# projeto_2.net
KiCad netlist of a schematic drawn in EAGLE
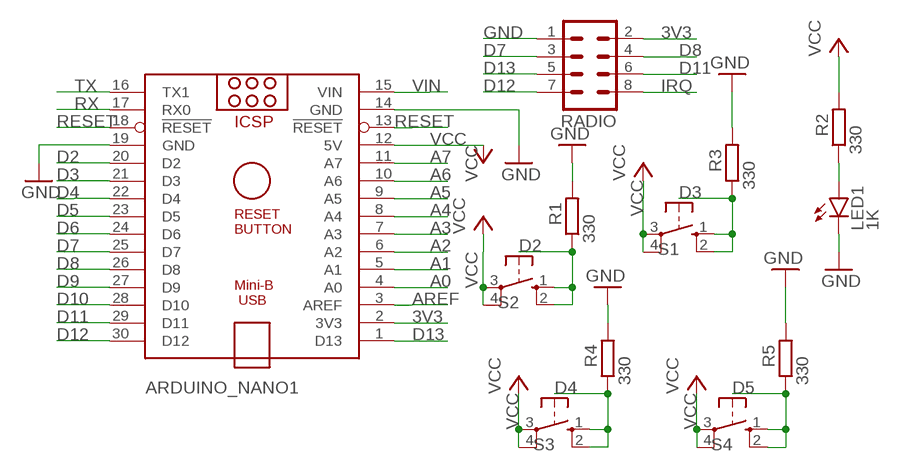
[diagram p0: schematic, sheet 1]

(export (version "E")
  (design (tool "Eeschema 10.0.6"))
  (components
    (comp (ref "ARDUINO_NANO1")
      (value "ARDUINO_NANO")
      (footprint "eagle-import:ARDUINO_NANO")
      (libsource (lib "eagle-import") (part "ARDUINO_NANO"))
    )
    (comp (ref "LED1")
      (value "1K")
      (footprint "eagle-import:LED5MM")
      (libsource (lib "eagle-import") (part "LED5MM"))
    )
    (comp (ref "R1")
      (value "330")
      (footprint "eagle-import:0204_7")
      (libsource (lib "eagle-import") (part "R-EU_0204/7"))
    )
    (comp (ref "R2")
      (value "330")
      (footprint "eagle-import:0204_7")
      (libsource (lib "eagle-import") (part "R-EU_0204/7"))
    )
    (comp (ref "R3")
      (value "330")
      (footprint "eagle-import:0204_7")
      (libsource (lib "eagle-import") (part "R-EU_0204/7"))
    )
    (comp (ref "R4")
      (value "330")
      (footprint "eagle-import:0204_7")
      (libsource (lib "eagle-import") (part "R-EU_0204/7"))
    )
    (comp (ref "R5")
      (value "330")
      (footprint "eagle-import:0204_7")
      (libsource (lib "eagle-import") (part "R-EU_0204/7"))
    )
    (comp (ref "RADIO")
      (value "MA04-2")
      (footprint "eagle-import:MA04-2")
      (libsource (lib "eagle-import") (part "MA04-2"))
    )
    (comp (ref "S1")
      (value "CHAVE 1")
      (footprint "eagle-import:B3F-10XX")
      (fields (field (name "MPN") "B3F-1000"))
      (libsource (lib "eagle-import") (part "10-XX"))
    )
    (comp (ref "S2")
      (value "CHAVE 1")
      (footprint "eagle-import:B3F-10XX")
      (fields (field (name "MPN") "B3F-1000"))
      (libsource (lib "eagle-import") (part "10-XX"))
    )
    (comp (ref "S3")
      (value "CHAVE 1")
      (footprint "eagle-import:B3F-10XX")
      (fields (field (name "MPN") "B3F-1000"))
      (libsource (lib "eagle-import") (part "10-XX"))
    )
    (comp (ref "S4")
      (value "CHAVE 1")
      (footprint "eagle-import:B3F-10XX")
      (fields (field (name "MPN") "B3F-1000"))
      (libsource (lib "eagle-import") (part "10-XX"))
    )
  )
  (nets
    (net (code "1") (name "/3V3") (class "Default")
      (node (ref "ARDUINO_NANO1") (pin "2") (pinfunction "3V3_2") (pintype "output"))
      (node (ref "RADIO") (pin "2") (pinfunction "2_2") (pintype "passive"))
    )
    (net (code "2") (name "/A0") (class "Default")
      (node (ref "ARDUINO_NANO1") (pin "4") (pinfunction "A0_4") (pintype "bidirectional"))
    )
    (net (code "3") (name "/A1") (class "Default")
      (node (ref "ARDUINO_NANO1") (pin "5") (pinfunction "A1_5") (pintype "bidirectional"))
    )
    (net (code "4") (name "/A2") (class "Default")
      (node (ref "ARDUINO_NANO1") (pin "6") (pinfunction "A2_6") (pintype "bidirectional"))
    )
    (net (code "5") (name "/A3") (class "Default")
      (node (ref "ARDUINO_NANO1") (pin "7") (pinfunction "A3_7") (pintype "bidirectional"))
    )
    (net (code "6") (name "/A4") (class "Default")
      (node (ref "ARDUINO_NANO1") (pin "8") (pinfunction "A4_8") (pintype "bidirectional"))
    )
    (net (code "7") (name "/A5") (class "Default")
      (node (ref "ARDUINO_NANO1") (pin "9") (pinfunction "A5_9") (pintype "bidirectional"))
    )
    (net (code "8") (name "/A6") (class "Default")
      (node (ref "ARDUINO_NANO1") (pin "10") (pinfunction "A6_10") (pintype "bidirectional"))
    )
    (net (code "9") (name "/A7") (class "Default")
      (node (ref "ARDUINO_NANO1") (pin "11") (pinfunction "A7_11") (pintype "bidirectional"))
    )
    (net (code "10") (name "/AREF") (class "Default")
      (node (ref "ARDUINO_NANO1") (pin "3") (pinfunction "AREF_3") (pintype "input"))
    )
    (net (code "11") (name "/D2") (class "Default")
      (node (ref "ARDUINO_NANO1") (pin "20") (pinfunction "D2_20") (pintype "bidirectional"))
      (node (ref "R1") (pin "1") (pinfunction "1_1") (pintype "passive"))
      (node (ref "S2") (pin "1") (pinfunction "S_1") (pintype "passive"))
      (node (ref "S2") (pin "2") (pinfunction "S1_2") (pintype "passive"))
    )
    (net (code "12") (name "/D3") (class "Default")
      (node (ref "ARDUINO_NANO1") (pin "21") (pinfunction "D3_21") (pintype "bidirectional"))
      (node (ref "R3") (pin "1") (pinfunction "1_1") (pintype "passive"))
      (node (ref "S1") (pin "1") (pinfunction "S_1") (pintype "passive"))
      (node (ref "S1") (pin "2") (pinfunction "S1_2") (pintype "passive"))
    )
    (net (code "13") (name "/D4") (class "Default")
      (node (ref "ARDUINO_NANO1") (pin "22") (pinfunction "D4_22") (pintype "bidirectional"))
      (node (ref "R4") (pin "1") (pinfunction "1_1") (pintype "passive"))
      (node (ref "S3") (pin "1") (pinfunction "S_1") (pintype "passive"))
      (node (ref "S3") (pin "2") (pinfunction "S1_2") (pintype "passive"))
    )
    (net (code "14") (name "/D5") (class "Default")
      (node (ref "ARDUINO_NANO1") (pin "23") (pinfunction "D5_23") (pintype "bidirectional"))
      (node (ref "R5") (pin "1") (pinfunction "1_1") (pintype "passive"))
      (node (ref "S4") (pin "1") (pinfunction "S_1") (pintype "passive"))
      (node (ref "S4") (pin "2") (pinfunction "S1_2") (pintype "passive"))
    )
    (net (code "15") (name "/D6") (class "Default")
      (node (ref "ARDUINO_NANO1") (pin "24") (pinfunction "D6_24") (pintype "bidirectional"))
    )
    (net (code "16") (name "/D7") (class "Default")
      (node (ref "ARDUINO_NANO1") (pin "25") (pinfunction "D7_25") (pintype "bidirectional"))
      (node (ref "RADIO") (pin "3") (pinfunction "3_3") (pintype "passive"))
    )
    (net (code "17") (name "/D8") (class "Default")
      (node (ref "ARDUINO_NANO1") (pin "26") (pinfunction "D8_26") (pintype "bidirectional"))
      (node (ref "RADIO") (pin "4") (pinfunction "4_4") (pintype "passive"))
    )
    (net (code "18") (name "/D9") (class "Default")
      (node (ref "ARDUINO_NANO1") (pin "27") (pinfunction "D9_27") (pintype "bidirectional"))
    )
    (net (code "19") (name "/D10") (class "Default")
      (node (ref "ARDUINO_NANO1") (pin "28") (pinfunction "D10_28") (pintype "bidirectional"))
    )
    (net (code "20") (name "/D11") (class "Default")
      (node (ref "ARDUINO_NANO1") (pin "29") (pinfunction "D11_29") (pintype "bidirectional"))
      (node (ref "RADIO") (pin "6") (pinfunction "6_6") (pintype "passive"))
    )
    (net (code "21") (name "/D12") (class "Default")
      (node (ref "ARDUINO_NANO1") (pin "30") (pinfunction "D12_30") (pintype "bidirectional"))
      (node (ref "RADIO") (pin "7") (pinfunction "7_7") (pintype "passive"))
    )
    (net (code "22") (name "/D13") (class "Default")
      (node (ref "ARDUINO_NANO1") (pin "1") (pinfunction "D13_1") (pintype "bidirectional"))
      (node (ref "RADIO") (pin "5") (pinfunction "5_5") (pintype "passive"))
    )
    (net (code "23") (name "/IRQ") (class "Default")
      (node (ref "RADIO") (pin "8") (pinfunction "8_8") (pintype "passive"))
    )
    (net (code "24") (name "/RESET") (class "Default")
      (node (ref "ARDUINO_NANO1") (pin "13") (pinfunction "~{RESET}_13") (pintype "input"))
      (node (ref "ARDUINO_NANO1") (pin "18") (pinfunction "~{RESET}_18") (pintype "input"))
    )
    (net (code "25") (name "/RX") (class "Default")
      (node (ref "ARDUINO_NANO1") (pin "17") (pinfunction "RX0_17") (pintype "bidirectional"))
    )
    (net (code "26") (name "/TX") (class "Default")
      (node (ref "ARDUINO_NANO1") (pin "16") (pinfunction "TX1_16") (pintype "bidirectional"))
    )
    (net (code "27") (name "/VIN") (class "Default")
      (node (ref "ARDUINO_NANO1") (pin "15") (pinfunction "VIN_15") (pintype "power_in"))
    )
    (net (code "28") (name "GND") (class "Default")
      (node (ref "ARDUINO_NANO1") (pin "14") (pinfunction "GND_14") (pintype "power_in"))
      (node (ref "ARDUINO_NANO1") (pin "19") (pinfunction "GND_19") (pintype "power_in"))
      (node (ref "LED1") (pin "K") (pinfunction "C_K") (pintype "passive"))
      (node (ref "R1") (pin "2") (pinfunction "2_2") (pintype "passive"))
      (node (ref "R3") (pin "2") (pinfunction "2_2") (pintype "passive"))
      (node (ref "R4") (pin "2") (pinfunction "2_2") (pintype "passive"))
      (node (ref "R5") (pin "2") (pinfunction "2_2") (pintype "passive"))
      (node (ref "RADIO") (pin "1") (pinfunction "1_1") (pintype "passive"))
    )
    (net (code "29") (name "Net-(LED1-PadA)") (class "Default")
      (node (ref "LED1") (pin "A") (pinfunction "A_A") (pintype "passive"))
      (node (ref "R2") (pin "1") (pinfunction "1_1") (pintype "passive"))
    )
    (net (code "30") (name "VCC") (class "Default")
      (node (ref "ARDUINO_NANO1") (pin "12") (pinfunction "5V_12") (pintype "power_in"))
      (node (ref "R2") (pin "2") (pinfunction "2_2") (pintype "passive"))
      (node (ref "S1") (pin "3") (pinfunction "P_3") (pintype "passive"))
      (node (ref "S1") (pin "4") (pinfunction "P1_4") (pintype "passive"))
      (node (ref "S2") (pin "3") (pinfunction "P_3") (pintype "passive"))
      (node (ref "S2") (pin "4") (pinfunction "P1_4") (pintype "passive"))
      (node (ref "S3") (pin "3") (pinfunction "P_3") (pintype "passive"))
      (node (ref "S3") (pin "4") (pinfunction "P1_4") (pintype "passive"))
      (node (ref "S4") (pin "3") (pinfunction "P_3") (pintype "passive"))
      (node (ref "S4") (pin "4") (pinfunction "P1_4") (pintype "passive"))
    )
  )
)
